# pcb-full.net
KiCad netlist of a schematic drawn in EAGLE
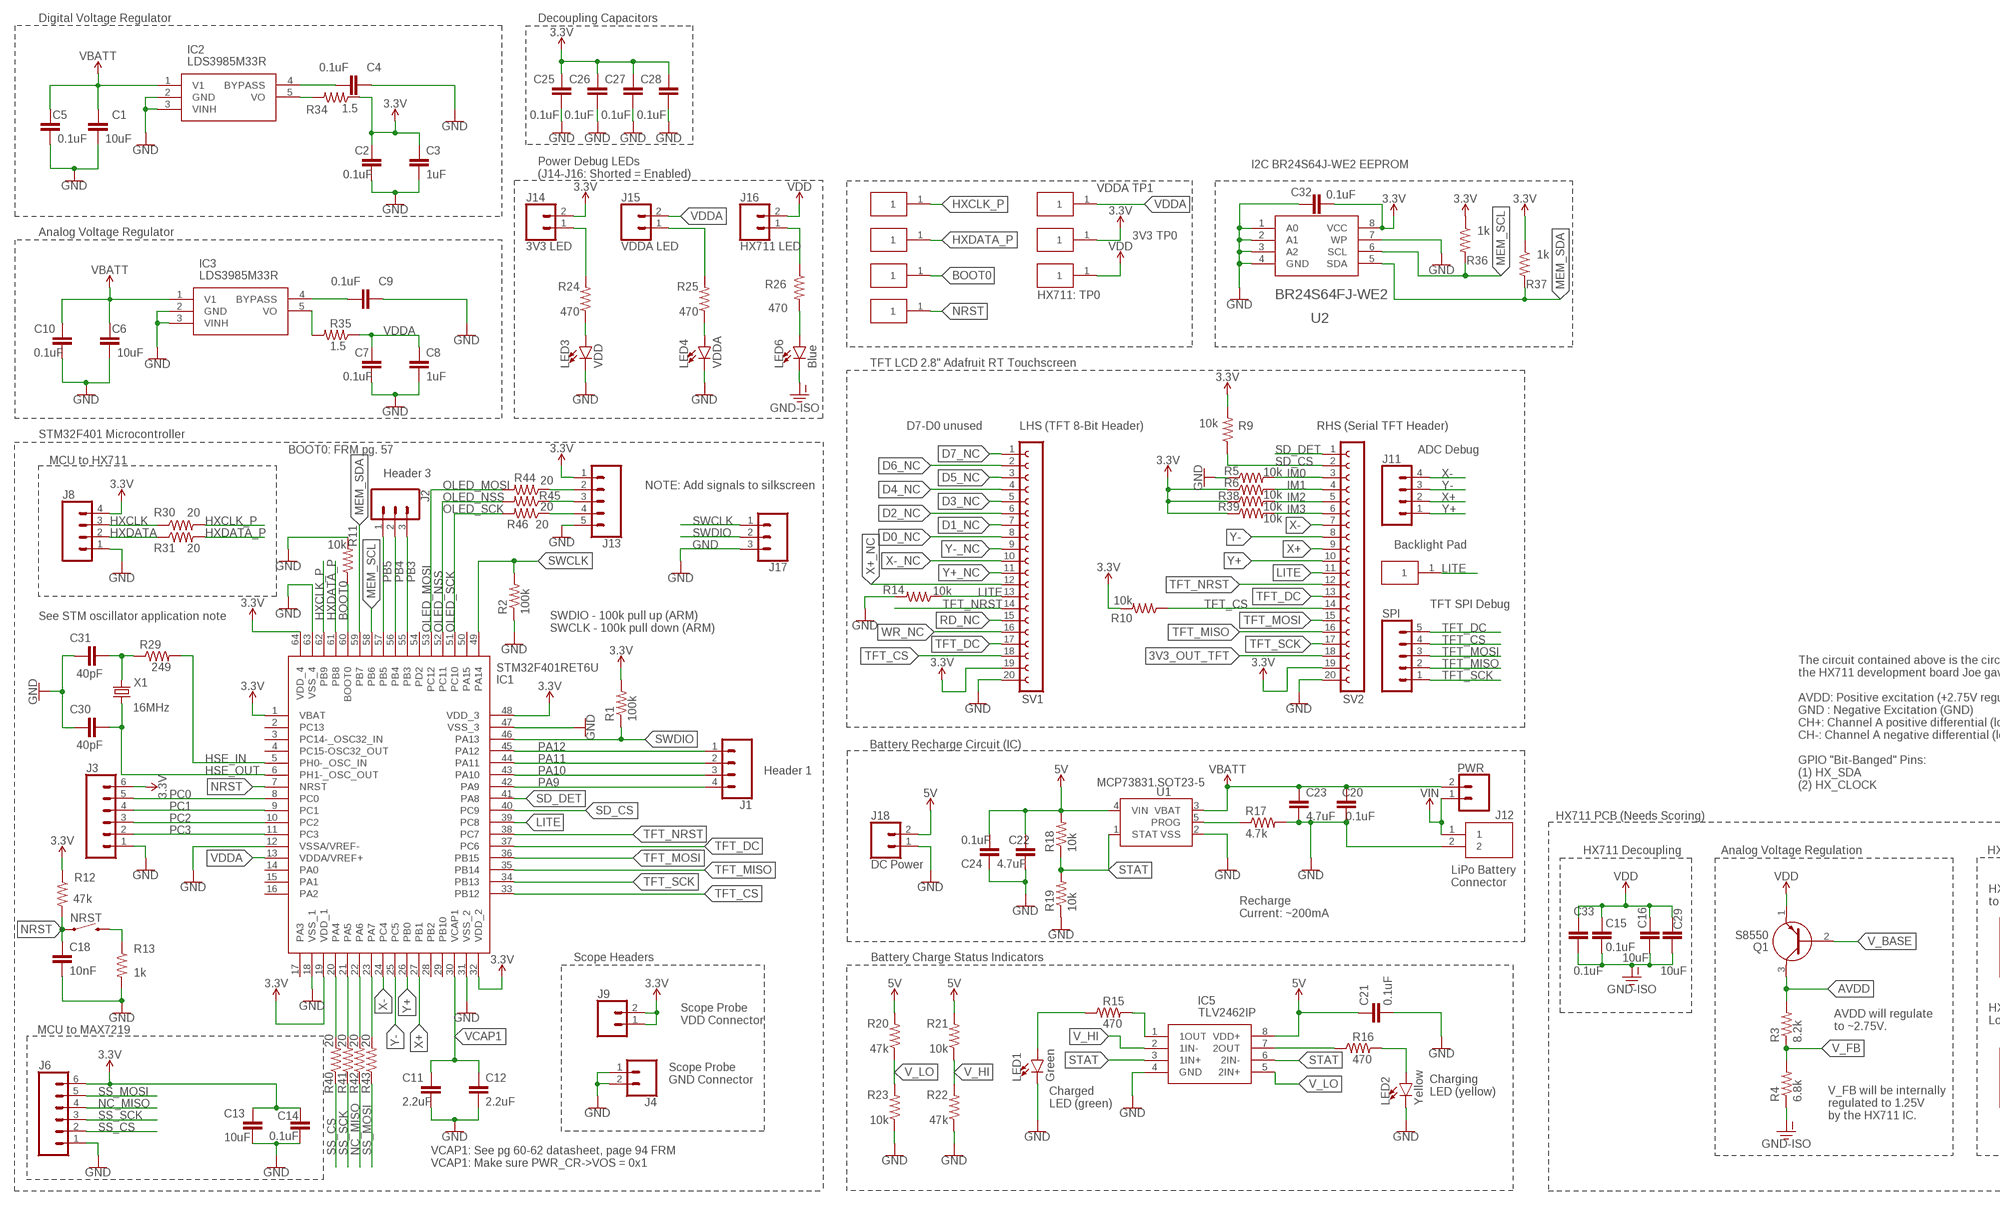
[diagram p0: schematic, sheet 1, part 1 of 2]
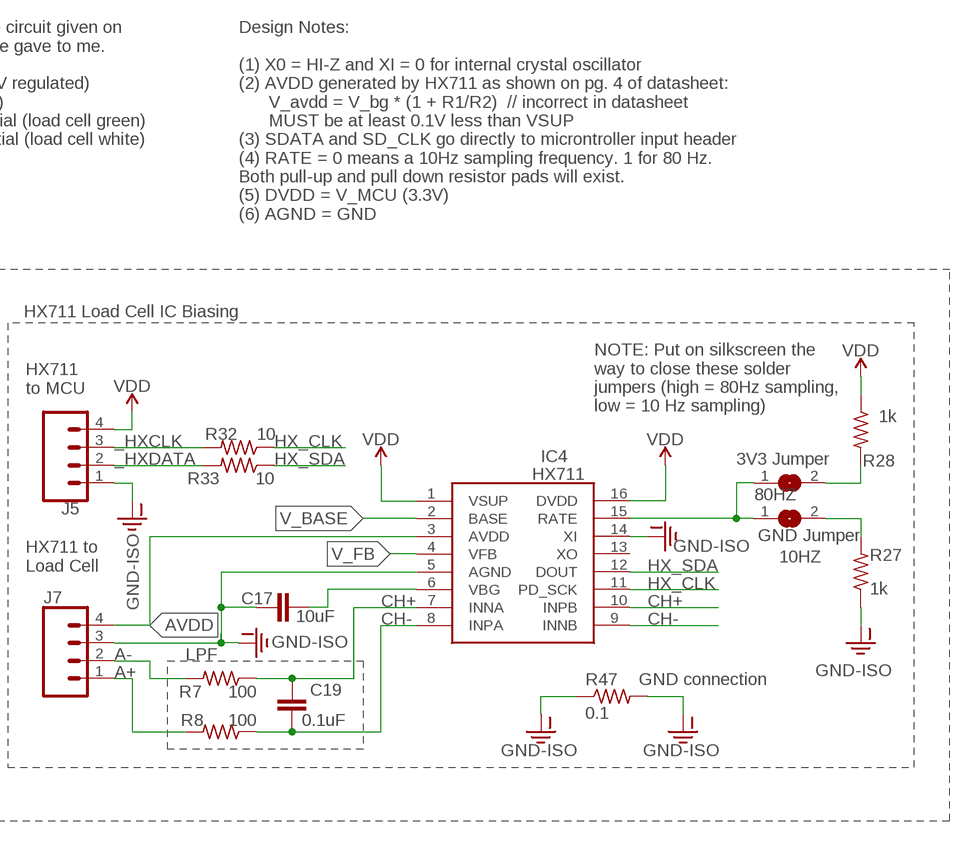
[diagram p1: schematic, sheet 1, part 2 of 2]

(export (version "E")
  (design (tool "Eeschema 10.0.6"))
  (components
    (comp (ref "10HZ")
      (value "GND Jumper")
      (footprint "eagle-import:SJ")
      (libsource (lib "eagle-import") (part "SJ"))
    )
    (comp (ref "80HZ")
      (value "3V3 Jumper")
      (footprint "eagle-import:SJ")
      (libsource (lib "eagle-import") (part "SJ"))
    )
    (comp (ref "C1")
      (value "10uF")
      (footprint "eagle-import:C0603")
      (libsource (lib "eagle-import") (part "CAPACITOR0603"))
    )
    (comp (ref "C2")
      (value "0.1uF")
      (footprint "eagle-import:C0603")
      (libsource (lib "eagle-import") (part "CAPACITOR0603"))
    )
    (comp (ref "C3")
      (value "1uF")
      (footprint "eagle-import:C0603")
      (libsource (lib "eagle-import") (part "CAPACITOR0603"))
    )
    (comp (ref "C4")
      (value "0.1uF")
      (footprint "eagle-import:C0603")
      (libsource (lib "eagle-import") (part "CAPACITOR0603"))
    )
    (comp (ref "C5")
      (value "0.1uF")
      (footprint "eagle-import:C0603")
      (libsource (lib "eagle-import") (part "CAPACITOR0603"))
    )
    (comp (ref "C6")
      (value "10uF")
      (footprint "eagle-import:C0603")
      (libsource (lib "eagle-import") (part "CAPACITOR0603"))
    )
    (comp (ref "C7")
      (value "0.1uF")
      (footprint "eagle-import:C0603")
      (libsource (lib "eagle-import") (part "CAPACITOR0603"))
    )
    (comp (ref "C8")
      (value "1uF")
      (footprint "eagle-import:C0603")
      (libsource (lib "eagle-import") (part "CAPACITOR0603"))
    )
    (comp (ref "C9")
      (value "0.1uF")
      (footprint "eagle-import:C0603")
      (libsource (lib "eagle-import") (part "CAPACITOR0603"))
    )
    (comp (ref "C10")
      (value "0.1uF")
      (footprint "eagle-import:C0603")
      (libsource (lib "eagle-import") (part "CAPACITOR0603"))
    )
    (comp (ref "C11")
      (value "2.2uF")
      (footprint "eagle-import:C0603")
      (libsource (lib "eagle-import") (part "CAPACITOR0603"))
    )
    (comp (ref "C12")
      (value "2.2uF")
      (footprint "eagle-import:C0603")
      (libsource (lib "eagle-import") (part "CAPACITOR0603"))
    )
    (comp (ref "C13")
      (value "10uF")
      (footprint "eagle-import:C0603")
      (libsource (lib "eagle-import") (part "CAPACITOR0603"))
    )
    (comp (ref "C14")
      (value "0.1uF")
      (footprint "eagle-import:C0603")
      (libsource (lib "eagle-import") (part "CAPACITOR0603"))
    )
    (comp (ref "C15")
      (value "0.1uF")
      (footprint "eagle-import:C0603")
      (libsource (lib "eagle-import") (part "CAPACITOR0603"))
    )
    (comp (ref "C16")
      (value "10uF")
      (footprint "eagle-import:C0603")
      (libsource (lib "eagle-import") (part "CAPACITOR0603"))
    )
    (comp (ref "C17")
      (value "10uF")
      (footprint "eagle-import:C0603")
      (libsource (lib "eagle-import") (part "CAPACITOR0603"))
    )
    (comp (ref "C18")
      (value "10nF")
      (footprint "eagle-import:C0603")
      (libsource (lib "eagle-import") (part "CAPACITOR0603"))
    )
    (comp (ref "C19")
      (value "0.1uF")
      (footprint "eagle-import:C0603")
      (libsource (lib "eagle-import") (part "CAPACITOR0603"))
    )
    (comp (ref "C20")
      (value "0.1uF")
      (footprint "eagle-import:C0603")
      (libsource (lib "eagle-import") (part "CAPACITOR0603"))
    )
    (comp (ref "C21")
      (value "0.1uF")
      (footprint "eagle-import:C0603")
      (libsource (lib "eagle-import") (part "CAPACITOR0603"))
    )
    (comp (ref "C22")
      (value "4.7uF")
      (footprint "eagle-import:C5B4.5")
      (libsource (lib "eagle-import") (part "C5/4.5"))
    )
    (comp (ref "C23")
      (value "4.7uF")
      (footprint "eagle-import:C5B4.5")
      (libsource (lib "eagle-import") (part "C5/4.5"))
    )
    (comp (ref "C24")
      (value "0.1uF")
      (footprint "eagle-import:C0603")
      (libsource (lib "eagle-import") (part "CAPACITOR0603"))
    )
    (comp (ref "C25")
      (value "0.1uF")
      (footprint "eagle-import:C0603")
      (libsource (lib "eagle-import") (part "CAPACITOR0603"))
    )
    (comp (ref "C26")
      (value "0.1uF")
      (footprint "eagle-import:C0603")
      (libsource (lib "eagle-import") (part "CAPACITOR0603"))
    )
    (comp (ref "C27")
      (value "0.1uF")
      (footprint "eagle-import:C0603")
      (libsource (lib "eagle-import") (part "CAPACITOR0603"))
    )
    (comp (ref "C28")
      (value "0.1uF")
      (footprint "eagle-import:C0603")
      (libsource (lib "eagle-import") (part "CAPACITOR0603"))
    )
    (comp (ref "C29")
      (value "10uF")
      (footprint "eagle-import:C0603")
      (libsource (lib "eagle-import") (part "CAPACITOR0603"))
    )
    (comp (ref "C30")
      (value "40pF")
      (footprint "eagle-import:C0603")
      (libsource (lib "eagle-import") (part "CAPACITOR0603"))
    )
    (comp (ref "C31")
      (value "40pF")
      (footprint "eagle-import:C0603")
      (libsource (lib "eagle-import") (part "CAPACITOR0603"))
    )
    (comp (ref "C32")
      (value "0.1uF")
      (footprint "eagle-import:C0603")
      (libsource (lib "eagle-import") (part "CAPACITOR0603"))
    )
    (comp (ref "C33")
      (value "0.1uF")
      (footprint "eagle-import:C0603")
      (libsource (lib "eagle-import") (part "CAPACITOR0603"))
    )
    (comp (ref "IC1")
      (value "STM32F401RET6U")
      (footprint "eagle-import:QFP50P1200X1200X160-64N")
      (fields (field (name "MOUSER_PART_NUMBER") "511-STM32F401RET6U"))
      (libsource (lib "eagle-import") (part "STM32F401RET6U"))
    )
    (comp (ref "IC2")
      (value "LDS3985M33R")
      (footprint "eagle-import:SOT95P280X145-5N")
      (fields (field (name "MOUSER_PART_NUMBER") "511-LDS3985M33R"))
      (libsource (lib "eagle-import") (part "LDS3985M33R"))
    )
    (comp (ref "IC3")
      (value "LDS3985M33R")
      (footprint "eagle-import:SOT95P280X145-5N")
      (fields (field (name "MOUSER_PART_NUMBER") "511-LDS3985M33R"))
      (libsource (lib "eagle-import") (part "LDS3985M33R"))
    )
    (comp (ref "IC4")
      (value "HX711")
      (footprint "eagle-import:SOIC127P600X160-16N")
      (libsource (lib "eagle-import") (part "HX711"))
    )
    (comp (ref "IC5")
      (value "TLV2462IP")
      (footprint "eagle-import:DIP794W53P254L959H508Q8N")
      (fields (field (name "MOUSER_PART_NUMBER") "595-TLV2462IP"))
      (libsource (lib "eagle-import") (part "TLV2462IP"))
    )
    (comp (ref "J1")
      (value "CONN_04")
      (footprint "eagle-import:1X04")
      (libsource (lib "eagle-import") (part "CONN_04"))
    )
    (comp (ref "J2")
      (value "CONN_03")
      (footprint "eagle-import:1X03")
      (libsource (lib "eagle-import") (part "CONN_03"))
    )
    (comp (ref "J3")
      (value "CONN_06SILK_FEMALE_PTH")
      (footprint "eagle-import:1X06")
      (libsource (lib "eagle-import") (part "CONN_06SILK_FEMALE_PTH"))
    )
    (comp (ref "J4")
      (value "CONN_02")
      (footprint "eagle-import:1X02")
      (libsource (lib "eagle-import") (part "CONN_02"))
    )
    (comp (ref "J5")
      (value "CONN_04")
      (footprint "eagle-import:1X04")
      (libsource (lib "eagle-import") (part "CONN_04"))
    )
    (comp (ref "J6")
      (value "CONN_06SILK_FEMALE_PTH")
      (footprint "eagle-import:1X06")
      (libsource (lib "eagle-import") (part "CONN_06SILK_FEMALE_PTH"))
    )
    (comp (ref "J7")
      (value "CONN_04")
      (footprint "eagle-import:1X04")
      (libsource (lib "eagle-import") (part "CONN_04"))
    )
    (comp (ref "J8")
      (value "CONN_04")
      (footprint "eagle-import:1X04")
      (libsource (lib "eagle-import") (part "CONN_04"))
    )
    (comp (ref "J9")
      (value "CONN_02")
      (footprint "eagle-import:1X02")
      (libsource (lib "eagle-import") (part "CONN_02"))
    )
    (comp (ref "J11")
      (value "CONN_04")
      (footprint "eagle-import:1X04")
      (libsource (lib "eagle-import") (part "CONN_04"))
    )
    (comp (ref "J12")
      (value "B2B-PH-K-S_LF__SN_")
      (footprint "eagle-import:SHDR2W50P0X200_1X2_590X450X600")
      (fields (field (name "ARROW_PART_NUMBER") "B2B-PH-K-S(LF)(SN)"))
      (libsource (lib "eagle-import") (part "B2B-PH-K-S_LF__SN_"))
    )
    (comp (ref "J13")
      (value "CONN_05")
      (footprint "eagle-import:1X05")
      (libsource (lib "eagle-import") (part "CONN_05"))
    )
    (comp (ref "J14")
      (value "3V3 LED")
      (footprint "eagle-import:1X02")
      (libsource (lib "eagle-import") (part "CONN_02"))
    )
    (comp (ref "J15")
      (value "VDDA LED")
      (footprint "eagle-import:1X02")
      (libsource (lib "eagle-import") (part "CONN_02"))
    )
    (comp (ref "J16")
      (value "HX711 LED")
      (footprint "eagle-import:1X02")
      (libsource (lib "eagle-import") (part "CONN_02"))
    )
    (comp (ref "J17")
      (value "CONN_03")
      (footprint "eagle-import:1X03")
      (libsource (lib "eagle-import") (part "CONN_03"))
    )
    (comp (ref "J18")
      (value "DC Power")
      (footprint "eagle-import:1X02")
      (libsource (lib "eagle-import") (part "CONN_02"))
    )
    (comp (ref "LED1")
      (value "Green")
      (footprint "eagle-import:LED-0603")
      (libsource (lib "eagle-import") (part "LED0603"))
    )
    (comp (ref "LED2")
      (value "Yellow")
      (footprint "eagle-import:LED-0603")
      (libsource (lib "eagle-import") (part "LED0603"))
    )
    (comp (ref "LED3")
      (value "VDD")
      (footprint "eagle-import:LED-0603")
      (libsource (lib "eagle-import") (part "LED0603"))
    )
    (comp (ref "LED4")
      (value "VDDA")
      (footprint "eagle-import:LED-0603")
      (libsource (lib "eagle-import") (part "LED0603"))
    )
    (comp (ref "LED6")
      (value "Blue")
      (footprint "eagle-import:LED-0603")
      (libsource (lib "eagle-import") (part "LED0603"))
    )
    (comp (ref "NRST")
      (value "MOMENTARY-SWITCH-SPST-SMD-5.2-REDUNDANT")
      (footprint "eagle-import:TACTILE_SWITCH_SMD_5.2MM")
      (libsource (lib "eagle-import") (part "MOMENTARY-SWITCH-SPST-SMD-5.2-REDUNDANT"))
    )
    (comp (ref "PWR")
      (value "CONN_02")
      (footprint "eagle-import:1X02")
      (libsource (lib "eagle-import") (part "CONN_02"))
    )
    (comp (ref "Q1")
      (value "S8550")
      (footprint "eagle-import:MJE13001TP")
      (libsource (lib "eagle-import") (part "S8550"))
    )
    (comp (ref "R1")
      (value "100k")
      (footprint "eagle-import:R0603")
      (libsource (lib "eagle-import") (part "RESISTOR0603"))
    )
    (comp (ref "R2")
      (value "100k")
      (footprint "eagle-import:R0603")
      (libsource (lib "eagle-import") (part "RESISTOR0603"))
    )
    (comp (ref "R3")
      (value "8.2k")
      (footprint "eagle-import:R0603")
      (libsource (lib "eagle-import") (part "RESISTOR0603"))
    )
    (comp (ref "R4")
      (value "6.8k")
      (footprint "eagle-import:R0603")
      (libsource (lib "eagle-import") (part "RESISTOR0603"))
    )
    (comp (ref "R5")
      (value "10k")
      (footprint "eagle-import:R0603")
      (libsource (lib "eagle-import") (part "RESISTOR0603"))
    )
    (comp (ref "R6")
      (value "10k")
      (footprint "eagle-import:R0603")
      (libsource (lib "eagle-import") (part "RESISTOR0603"))
    )
    (comp (ref "R7")
      (value "100")
      (footprint "eagle-import:R0603")
      (libsource (lib "eagle-import") (part "RESISTOR0603"))
    )
    (comp (ref "R8")
      (value "100")
      (footprint "eagle-import:R0603")
      (libsource (lib "eagle-import") (part "RESISTOR0603"))
    )
    (comp (ref "R9")
      (value "10k")
      (footprint "eagle-import:R0603")
      (libsource (lib "eagle-import") (part "RESISTOR0603"))
    )
    (comp (ref "R10")
      (value "10k")
      (footprint "eagle-import:R0603")
      (libsource (lib "eagle-import") (part "RESISTOR0603"))
    )
    (comp (ref "R11")
      (value "10k")
      (footprint "eagle-import:R0603")
      (libsource (lib "eagle-import") (part "RESISTOR0603"))
    )
    (comp (ref "R12")
      (value "47k")
      (footprint "eagle-import:R0603")
      (libsource (lib "eagle-import") (part "RESISTOR0603"))
    )
    (comp (ref "R13")
      (value "1k")
      (footprint "eagle-import:R0603")
      (libsource (lib "eagle-import") (part "RESISTOR0603"))
    )
    (comp (ref "R14")
      (value "10k")
      (footprint "eagle-import:R0603")
      (libsource (lib "eagle-import") (part "RESISTOR0603"))
    )
    (comp (ref "R15")
      (value "470")
      (footprint "eagle-import:R0603")
      (libsource (lib "eagle-import") (part "RESISTOR0603"))
    )
    (comp (ref "R16")
      (value "470")
      (footprint "eagle-import:R0603")
      (libsource (lib "eagle-import") (part "RESISTOR0603"))
    )
    (comp (ref "R17")
      (value "4.7k")
      (footprint "eagle-import:R0603")
      (libsource (lib "eagle-import") (part "RESISTOR0603"))
    )
    (comp (ref "R18")
      (value "10k")
      (footprint "eagle-import:R0603")
      (libsource (lib "eagle-import") (part "RESISTOR0603"))
    )
    (comp (ref "R19")
      (value "10k")
      (footprint "eagle-import:R0603")
      (libsource (lib "eagle-import") (part "RESISTOR0603"))
    )
    (comp (ref "R20")
      (value "47k")
      (footprint "eagle-import:R0603")
      (libsource (lib "eagle-import") (part "RESISTOR0603"))
    )
    (comp (ref "R21")
      (value "10k")
      (footprint "eagle-import:R0603")
      (libsource (lib "eagle-import") (part "RESISTOR0603"))
    )
    (comp (ref "R22")
      (value "47k")
      (footprint "eagle-import:R0603")
      (libsource (lib "eagle-import") (part "RESISTOR0603"))
    )
    (comp (ref "R23")
      (value "10k")
      (footprint "eagle-import:R0603")
      (libsource (lib "eagle-import") (part "RESISTOR0603"))
    )
    (comp (ref "R24")
      (value "470")
      (footprint "eagle-import:R0603")
      (libsource (lib "eagle-import") (part "RESISTOR0603"))
    )
    (comp (ref "R25")
      (value "470")
      (footprint "eagle-import:R0603")
      (libsource (lib "eagle-import") (part "RESISTOR0603"))
    )
    (comp (ref "R26")
      (value "470")
      (footprint "eagle-import:R0603")
      (libsource (lib "eagle-import") (part "RESISTOR0603"))
    )
    (comp (ref "R27")
      (value "1k")
      (footprint "eagle-import:R0603")
      (libsource (lib "eagle-import") (part "RESISTOR0603"))
    )
    (comp (ref "R28")
      (value "1k")
      (footprint "eagle-import:R0603")
      (libsource (lib "eagle-import") (part "RESISTOR0603"))
    )
    (comp (ref "R29")
      (value "249")
      (footprint "eagle-import:R0603")
      (libsource (lib "eagle-import") (part "RESISTOR0603"))
    )
    (comp (ref "R30")
      (value "20")
      (footprint "eagle-import:R0603")
      (libsource (lib "eagle-import") (part "RESISTOR0603"))
    )
    (comp (ref "R31")
      (value "20")
      (footprint "eagle-import:R0603")
      (libsource (lib "eagle-import") (part "RESISTOR0603"))
    )
    (comp (ref "R32")
      (value "10")
      (footprint "eagle-import:R0603")
      (libsource (lib "eagle-import") (part "RESISTOR0603"))
    )
    (comp (ref "R33")
      (value "10")
      (footprint "eagle-import:R0603")
      (libsource (lib "eagle-import") (part "RESISTOR0603"))
    )
    (comp (ref "R34")
      (value "1.5")
      (footprint "eagle-import:R0603")
      (libsource (lib "eagle-import") (part "RESISTOR0603"))
    )
    (comp (ref "R35")
      (value "1.5")
      (footprint "eagle-import:R0603")
      (libsource (lib "eagle-import") (part "RESISTOR0603"))
    )
    (comp (ref "R36")
      (value "1k")
      (footprint "eagle-import:R0603")
      (libsource (lib "eagle-import") (part "RESISTOR0603"))
    )
    (comp (ref "R37")
      (value "1k")
      (footprint "eagle-import:R0603")
      (libsource (lib "eagle-import") (part "RESISTOR0603"))
    )
    (comp (ref "R38")
      (value "10k")
      (footprint "eagle-import:R0603")
      (libsource (lib "eagle-import") (part "RESISTOR0603"))
    )
    (comp (ref "R39")
      (value "10k")
      (footprint "eagle-import:R0603")
      (libsource (lib "eagle-import") (part "RESISTOR0603"))
    )
    (comp (ref "R40")
      (value "20")
      (footprint "eagle-import:R0603")
      (libsource (lib "eagle-import") (part "RESISTOR0603"))
    )
    (comp (ref "R41")
      (value "20")
      (footprint "eagle-import:R0603")
      (libsource (lib "eagle-import") (part "RESISTOR0603"))
    )
    (comp (ref "R42")
      (value "20")
      (footprint "eagle-import:R0603")
      (libsource (lib "eagle-import") (part "RESISTOR0603"))
    )
    (comp (ref "R43")
      (value "20")
      (footprint "eagle-import:R0603")
      (libsource (lib "eagle-import") (part "RESISTOR0603"))
    )
    (comp (ref "R44")
      (value "20")
      (footprint "eagle-import:R0603")
      (libsource (lib "eagle-import") (part "RESISTOR0603"))
    )
    (comp (ref "R45")
      (value "20")
      (footprint "eagle-import:R0603")
      (libsource (lib "eagle-import") (part "RESISTOR0603"))
    )
    (comp (ref "R46")
      (value "20")
      (footprint "eagle-import:R0603")
      (libsource (lib "eagle-import") (part "RESISTOR0603"))
    )
    (comp (ref "R47")
      (value "0.1")
      (footprint "eagle-import:R0603")
      (libsource (lib "eagle-import") (part "RESISTOR0603"))
    )
    (comp (ref "SPI")
      (value "CONN_05")
      (footprint "eagle-import:1X05")
      (libsource (lib "eagle-import") (part "CONN_05"))
    )
    (comp (ref "SV1")
      (value "LHS (TFT 8-Bit Header)")
      (footprint "eagle-import:FE20")
      (libsource (lib "eagle-import") (part "FE20-1"))
    )
    (comp (ref "SV2")
      (value "RHS (Serial TFT Header)")
      (footprint "eagle-import:FE20")
      (libsource (lib "eagle-import") (part "FE20-1"))
    )
    (comp (ref "U$1")
      (value "TP1")
      (footprint "eagle-import:PAD")
      (libsource (lib "eagle-import") (part "PAD"))
    )
    (comp (ref "U$2")
      (value "TP3")
      (footprint "eagle-import:PAD")
      (libsource (lib "eagle-import") (part "PAD"))
    )
    (comp (ref "U$3")
      (value "TP4")
      (footprint "eagle-import:PAD")
      (libsource (lib "eagle-import") (part "PAD"))
    )
    (comp (ref "U$4")
      (value "TP5")
      (footprint "eagle-import:PAD")
      (libsource (lib "eagle-import") (part "PAD"))
    )
    (comp (ref "U$5")
      (value "TP6")
      (footprint "eagle-import:PAD")
      (libsource (lib "eagle-import") (part "PAD"))
    )
    (comp (ref "U$6")
      (value "TP1")
      (footprint "eagle-import:PAD")
      (libsource (lib "eagle-import") (part "PAD"))
    )
    (comp (ref "U$7")
      (value "TP0")
      (footprint "eagle-import:PAD")
      (libsource (lib "eagle-import") (part "PAD"))
    )
    (comp (ref "U$8")
      (value "TP2")
      (footprint "eagle-import:PAD")
      (libsource (lib "eagle-import") (part "PAD"))
    )
    (comp (ref "U1")
      (value "MCP73831.SOT23-5")
      (footprint "eagle-import:SOT23-5")
      (libsource (lib "eagle-import") (part "MCP73831.SOT23-5"))
    )
    (comp (ref "U2")
      (value "BR24S64FJ-WE2")
      (footprint "eagle-import:SOIC8")
      (libsource (lib "eagle-import") (part "BR24S64FJ-WE2"))
    )
    (comp (ref "X1")
      (value "16MHz")
      (footprint "eagle-import:HC49_S")
      (libsource (lib "eagle-import") (part "CRYSTALHC49S"))
    )
  )
  (nets
    (net (code "1") (name "/A+") (class "Default")
      (node (ref "J7") (pin "1") (pinfunction "1_1") (pintype "passive"))
      (node (ref "R8") (pin "2") (pinfunction "2_2") (pintype "passive"))
    )
    (net (code "2") (name "/A-") (class "Default")
      (node (ref "J7") (pin "2") (pinfunction "2_2") (pintype "passive"))
      (node (ref "R7") (pin "2") (pinfunction "2_2") (pintype "passive"))
    )
    (net (code "3") (name "/CH+") (class "Default")
      (node (ref "C19") (pin "1") (pinfunction "1_1") (pintype "passive"))
      (node (ref "IC4") (pin "10") (pinfunction "INPB_10") (pintype "bidirectional"))
      (node (ref "IC4") (pin "7") (pinfunction "INNA_7") (pintype "bidirectional"))
      (node (ref "R7") (pin "1") (pinfunction "1_1") (pintype "passive"))
    )
    (net (code "4") (name "/CH-") (class "Default")
      (node (ref "C19") (pin "2") (pinfunction "2_2") (pintype "passive"))
      (node (ref "IC4") (pin "8") (pinfunction "INPA_8") (pintype "bidirectional"))
      (node (ref "IC4") (pin "9") (pinfunction "INNB_9") (pintype "bidirectional"))
      (node (ref "R8") (pin "1") (pinfunction "1_1") (pintype "passive"))
    )
    (net (code "5") (name "/HSE_IN") (class "Default")
      (node (ref "IC1") (pin "5") (pinfunction "PH0-_OSC_IN_5") (pintype "bidirectional"))
      (node (ref "R29") (pin "2") (pinfunction "2_2") (pintype "passive"))
    )
    (net (code "6") (name "/HSE_OUT") (class "Default")
      (node (ref "C30") (pin "2") (pinfunction "2_2") (pintype "passive"))
      (node (ref "IC1") (pin "6") (pinfunction "PH1-_OSC_OUT_6") (pintype "bidirectional"))
      (node (ref "X1") (pin "1") (pinfunction "1_1") (pintype "passive"))
    )
    (net (code "7") (name "/HXCLK") (class "Default")
      (node (ref "J8") (pin "3") (pinfunction "3_3") (pintype "passive"))
      (node (ref "R30") (pin "1") (pinfunction "1_1") (pintype "passive"))
    )
    (net (code "8") (name "/HXDATA") (class "Default")
      (node (ref "J8") (pin "2") (pinfunction "2_2") (pintype "passive"))
      (node (ref "R31") (pin "1") (pinfunction "1_1") (pintype "passive"))
    )
    (net (code "9") (name "/HX_CLK") (class "Default")
      (node (ref "IC4") (pin "11") (pinfunction "PD_SCK_11") (pintype "bidirectional"))
      (node (ref "R32") (pin "1") (pinfunction "1_1") (pintype "passive"))
    )
    (net (code "10") (name "/HX_SDA") (class "Default")
      (node (ref "IC4") (pin "12") (pinfunction "DOUT_12") (pintype "bidirectional"))
      (node (ref "R33") (pin "1") (pinfunction "1_1") (pintype "passive"))
    )
    (net (code "11") (name "/IM0") (class "Default")
      (node (ref "R5") (pin "2") (pinfunction "2_2") (pintype "passive"))
      (node (ref "SV2") (pin "3") (pinfunction "3_3") (pintype "passive"))
    )
    (net (code "12") (name "/IM1") (class "Default")
      (node (ref "R6") (pin "2") (pinfunction "2_2") (pintype "passive"))
      (node (ref "SV2") (pin "4") (pinfunction "4_4") (pintype "passive"))
    )
    (net (code "13") (name "/IM2") (class "Default")
      (node (ref "R38") (pin "2") (pinfunction "2_2") (pintype "passive"))
      (node (ref "SV2") (pin "5") (pinfunction "5_5") (pintype "passive"))
    )
    (net (code "14") (name "/IM3") (class "Default")
      (node (ref "R39") (pin "2") (pinfunction "2_2") (pintype "passive"))
      (node (ref "SV2") (pin "6") (pinfunction "6_6") (pintype "passive"))
    )
    (net (code "15") (name "/NC_MISO") (class "Default")
      (node (ref "J6") (pin "4") (pinfunction "4_4") (pintype "passive"))
      (node (ref "R42") (pin "1") (pinfunction "1_1") (pintype "passive"))
    )
    (net (code "16") (name "/OLED_MOSI") (class "Default")
      (node (ref "IC1") (pin "53") (pinfunction "PC12_53") (pintype "bidirectional"))
      (node (ref "R44") (pin "2") (pinfunction "2_2") (pintype "passive"))
    )
    (net (code "17") (name "/OLED_NSS") (class "Default")
      (node (ref "IC1") (pin "52") (pinfunction "PC11_52") (pintype "bidirectional"))
      (node (ref "R45") (pin "2") (pinfunction "2_2") (pintype "passive"))
    )
    (net (code "18") (name "/OLED_SCK") (class "Default")
      (node (ref "IC1") (pin "51") (pinfunction "PC10_51") (pintype "bidirectional"))
      (node (ref "R46") (pin "2") (pinfunction "2_2") (pintype "passive"))
    )
    (net (code "19") (name "/PA9") (class "Default")
      (node (ref "IC1") (pin "42") (pinfunction "PA9_42") (pintype "bidirectional"))
      (node (ref "J1") (pin "4") (pinfunction "4_4") (pintype "passive"))
    )
    (net (code "20") (name "/PA10") (class "Default")
      (node (ref "IC1") (pin "43") (pinfunction "PA10_43") (pintype "bidirectional"))
      (node (ref "J1") (pin "3") (pinfunction "3_3") (pintype "passive"))
    )
    (net (code "21") (name "/PA11") (class "Default")
      (node (ref "IC1") (pin "44") (pinfunction "PA11_44") (pintype "bidirectional"))
      (node (ref "J1") (pin "2") (pinfunction "2_2") (pintype "passive"))
    )
    (net (code "22") (name "/PA12") (class "Default")
      (node (ref "IC1") (pin "45") (pinfunction "PA12_45") (pintype "bidirectional"))
      (node (ref "J1") (pin "1") (pinfunction "1_1") (pintype "passive"))
    )
    (net (code "23") (name "/PB3") (class "Default")
      (node (ref "IC1") (pin "55") (pinfunction "PB3_55") (pintype "bidirectional"))
      (node (ref "J2") (pin "3") (pinfunction "3_3") (pintype "passive"))
    )
    (net (code "24") (name "/PB4") (class "Default")
      (node (ref "IC1") (pin "56") (pinfunction "PB4_56") (pintype "bidirectional"))
      (node (ref "J2") (pin "2") (pinfunction "2_2") (pintype "passive"))
    )
    (net (code "25") (name "/PB5") (class "Default")
      (node (ref "IC1") (pin "57") (pinfunction "PB5_57") (pintype "bidirectional"))
      (node (ref "J2") (pin "1") (pinfunction "1_1") (pintype "passive"))
    )
    (net (code "26") (name "/PC0") (class "Default")
      (node (ref "IC1") (pin "8") (pinfunction "PC0_8") (pintype "bidirectional"))
      (node (ref "J3") (pin "5") (pinfunction "5_5") (pintype "passive"))
    )
    (net (code "27") (name "/PC1") (class "Default")
      (node (ref "IC1") (pin "9") (pinfunction "PC1_9") (pintype "bidirectional"))
      (node (ref "J3") (pin "4") (pinfunction "4_4") (pintype "passive"))
    )
    (net (code "28") (name "/PC2") (class "Default")
      (node (ref "IC1") (pin "10") (pinfunction "PC2_10") (pintype "bidirectional"))
      (node (ref "J3") (pin "3") (pinfunction "3_3") (pintype "passive"))
    )
    (net (code "29") (name "/PC3") (class "Default")
      (node (ref "IC1") (pin "11") (pinfunction "PC3_11") (pintype "bidirectional"))
      (node (ref "J3") (pin "2") (pinfunction "2_2") (pintype "passive"))
    )
    (net (code "30") (name "/SS_CS") (class "Default")
      (node (ref "J6") (pin "2") (pinfunction "2_2") (pintype "passive"))
      (node (ref "R40") (pin "1") (pinfunction "1_1") (pintype "passive"))
    )
    (net (code "31") (name "/SS_MOSI") (class "Default")
      (node (ref "J6") (pin "5") (pinfunction "5_5") (pintype "passive"))
      (node (ref "R43") (pin "1") (pinfunction "1_1") (pintype "passive"))
    )
    (net (code "32") (name "/SS_SCK") (class "Default")
      (node (ref "J6") (pin "3") (pinfunction "3_3") (pintype "passive"))
      (node (ref "R41") (pin "1") (pinfunction "1_1") (pintype "passive"))
    )
    (net (code "33") (name "/_HXCLK") (class "Default")
      (node (ref "J5") (pin "3") (pinfunction "3_3") (pintype "passive"))
      (node (ref "R32") (pin "2") (pinfunction "2_2") (pintype "passive"))
    )
    (net (code "34") (name "/_HXDATA") (class "Default")
      (node (ref "J5") (pin "2") (pinfunction "2_2") (pintype "passive"))
      (node (ref "R33") (pin "2") (pinfunction "2_2") (pintype "passive"))
    )
    (net (code "35") (name "3.3V") (class "Default")
      (node (ref "C13") (pin "1") (pinfunction "1_1") (pintype "passive"))
      (node (ref "C14") (pin "1") (pinfunction "1_1") (pintype "passive"))
      (node (ref "C2") (pin "1") (pinfunction "1_1") (pintype "passive"))
      (node (ref "C25") (pin "1") (pinfunction "1_1") (pintype "passive"))
      (node (ref "C26") (pin "1") (pinfunction "1_1") (pintype "passive"))
      (node (ref "C27") (pin "1") (pinfunction "1_1") (pintype "passive"))
      (node (ref "C28") (pin "1") (pinfunction "1_1") (pintype "passive"))
      (node (ref "C3") (pin "1") (pinfunction "1_1") (pintype "passive"))
      (node (ref "C32") (pin "2") (pinfunction "2_2") (pintype "passive"))
      (node (ref "IC1") (pin "1") (pinfunction "VBAT_1") (pintype "bidirectional"))
      (node (ref "IC1") (pin "19") (pinfunction "VDD_1_19") (pintype "bidirectional"))
      (node (ref "IC1") (pin "32") (pinfunction "VDD_2_32") (pintype "bidirectional"))
      (node (ref "IC1") (pin "48") (pinfunction "VDD_3_48") (pintype "bidirectional"))
      (node (ref "IC1") (pin "64") (pinfunction "VDD_4_64") (pintype "bidirectional"))
      (node (ref "J13") (pin "1") (pinfunction "1_1") (pintype "passive"))
      (node (ref "J14") (pin "2") (pinfunction "2_2") (pintype "passive"))
      (node (ref "J3") (pin "6") (pinfunction "6_6") (pintype "passive"))
      (node (ref "J6") (pin "6") (pinfunction "6_6") (pintype "passive"))
      (node (ref "J8") (pin "4") (pinfunction "4_4") (pintype "passive"))
      (node (ref "J9") (pin "1") (pinfunction "1_1") (pintype "passive"))
      (node (ref "J9") (pin "2") (pinfunction "2_2") (pintype "passive"))
      (node (ref "R1") (pin "2") (pinfunction "2_2") (pintype "passive"))
      (node (ref "R10") (pin "2") (pinfunction "2_2") (pintype "passive"))
      (node (ref "R12") (pin "1") (pinfunction "1_1") (pintype "passive"))
      (node (ref "R34") (pin "1") (pinfunction "1_1") (pintype "passive"))
      (node (ref "R36") (pin "1") (pinfunction "1_1") (pintype "passive"))
      (node (ref "R37") (pin "1") (pinfunction "1_1") (pintype "passive"))
      (node (ref "R38") (pin "1") (pinfunction "1_1") (pintype "passive"))
      (node (ref "R39") (pin "1") (pinfunction "1_1") (pintype "passive"))
      (node (ref "R6") (pin "1") (pinfunction "1_1") (pintype "passive"))
      (node (ref "R9") (pin "2") (pinfunction "2_2") (pintype "passive"))
      (node (ref "SV1") (pin "19") (pinfunction "19_19") (pintype "passive"))
      (node (ref "SV2") (pin "19") (pinfunction "19_19") (pintype "passive"))
      (node (ref "U$7") (pin "1") (pinfunction "1_1") (pintype "bidirectional"))
      (node (ref "U2") (pin "8") (pinfunction "VCC_8") (pintype "power_in"))
    )
    (net (code "36") (name "3V3_OUT_TFT") (class "Default")
      (node (ref "SV2") (pin "18") (pinfunction "18_18") (pintype "passive"))
    )
    (net (code "37") (name "5V") (class "Default")
      (node (ref "C21") (pin "1") (pinfunction "1_1") (pintype "passive"))
      (node (ref "C22") (pin "1") (pinfunction "1_1") (pintype "passive"))
      (node (ref "C24") (pin "2") (pinfunction "2_2") (pintype "passive"))
      (node (ref "IC5") (pin "8") (pinfunction "VDD+_8") (pintype "bidirectional"))
      (node (ref "J18") (pin "2") (pinfunction "2_2") (pintype "passive"))
      (node (ref "R18") (pin "2") (pinfunction "2_2") (pintype "passive"))
      (node (ref "R20") (pin "2") (pinfunction "2_2") (pintype "passive"))
      (node (ref "R21") (pin "2") (pinfunction "2_2") (pintype "passive"))
      (node (ref "U1") (pin "4") (pinfunction "VIN_4") (pintype "power_in"))
    )
    (net (code "38") (name "AVDD") (class "Default")
      (node (ref "IC4") (pin "3") (pinfunction "AVDD_3") (pintype "bidirectional"))
      (node (ref "J7") (pin "4") (pinfunction "4_4") (pintype "passive"))
      (node (ref "Q1") (pin "3") (pinfunction "C_3") (pintype "bidirectional"))
      (node (ref "R3") (pin "2") (pinfunction "2_2") (pintype "passive"))
    )
    (net (code "39") (name "BOOT0") (class "Default")
      (node (ref "IC1") (pin "60") (pinfunction "BOOT0_60") (pintype "bidirectional"))
      (node (ref "R11") (pin "1") (pinfunction "1_1") (pintype "passive"))
      (node (ref "U$4") (pin "1") (pinfunction "1_1") (pintype "bidirectional"))
    )
    (net (code "40") (name "D0_NC") (class "Default")
      (node (ref "SV1") (pin "8") (pinfunction "8_8") (pintype "passive"))
    )
    (net (code "41") (name "D1_NC") (class "Default")
      (node (ref "SV1") (pin "7") (pinfunction "7_7") (pintype "passive"))
    )
    (net (code "42") (name "D2_NC") (class "Default")
      (node (ref "SV1") (pin "6") (pinfunction "6_6") (pintype "passive"))
    )
    (net (code "43") (name "D3_NC") (class "Default")
      (node (ref "SV1") (pin "5") (pinfunction "5_5") (pintype "passive"))
    )
    (net (code "44") (name "D4_NC") (class "Default")
      (node (ref "SV1") (pin "4") (pinfunction "4_4") (pintype "passive"))
    )
    (net (code "45") (name "D5_NC") (class "Default")
      (node (ref "SV1") (pin "3") (pinfunction "3_3") (pintype "passive"))
    )
    (net (code "46") (name "D6_NC") (class "Default")
      (node (ref "SV1") (pin "2") (pinfunction "2_2") (pintype "passive"))
    )
    (net (code "47") (name "D7_NC") (class "Default")
      (node (ref "SV1") (pin "1") (pinfunction "1_1") (pintype "passive"))
    )
    (net (code "48") (name "GND") (class "Default")
      (node (ref "C1") (pin "2") (pinfunction "2_2") (pintype "passive"))
      (node (ref "C10") (pin "2") (pinfunction "2_2") (pintype "passive"))
      (node (ref "C11") (pin "2") (pinfunction "2_2") (pintype "passive"))
      (node (ref "C12") (pin "2") (pinfunction "2_2") (pintype "passive"))
      (node (ref "C13") (pin "2") (pinfunction "2_2") (pintype "passive"))
      (node (ref "C14") (pin "2") (pinfunction "2_2") (pintype "passive"))
      (node (ref "C18") (pin "2") (pinfunction "2_2") (pintype "passive"))
      (node (ref "C2") (pin "2") (pinfunction "2_2") (pintype "passive"))
      (node (ref "C20") (pin "2") (pinfunction "2_2") (pintype "passive"))
      (node (ref "C21") (pin "2") (pinfunction "2_2") (pintype "passive"))
      (node (ref "C22") (pin "2") (pinfunction "2_2") (pintype "passive"))
      (node (ref "C23") (pin "2") (pinfunction "2_2") (pintype "passive"))
      (node (ref "C24") (pin "1") (pinfunction "1_1") (pintype "passive"))
      (node (ref "C25") (pin "2") (pinfunction "2_2") (pintype "passive"))
      (node (ref "C26") (pin "2") (pinfunction "2_2") (pintype "passive"))
      (node (ref "C27") (pin "2") (pinfunction "2_2") (pintype "passive"))
      (node (ref "C28") (pin "2") (pinfunction "2_2") (pintype "passive"))
      (node (ref "C3") (pin "2") (pinfunction "2_2") (pintype "passive"))
      (node (ref "C30") (pin "1") (pinfunction "1_1") (pintype "passive"))
      (node (ref "C31") (pin "1") (pinfunction "1_1") (pintype "passive"))
      (node (ref "C32") (pin "1") (pinfunction "1_1") (pintype "passive"))
      (node (ref "C4") (pin "1") (pinfunction "1_1") (pintype "passive"))
      (node (ref "C5") (pin "2") (pinfunction "2_2") (pintype "passive"))
      (node (ref "C6") (pin "2") (pinfunction "2_2") (pintype "passive"))
      (node (ref "C7") (pin "2") (pinfunction "2_2") (pintype "passive"))
      (node (ref "C8") (pin "2") (pinfunction "2_2") (pintype "passive"))
      (node (ref "C9") (pin "1") (pinfunction "1_1") (pintype "passive"))
      (node (ref "IC1") (pin "12") (pinfunction "VSSA/VREF-_12") (pintype "bidirectional"))
      (node (ref "IC1") (pin "18") (pinfunction "VSS_1_18") (pintype "bidirectional"))
      (node (ref "IC1") (pin "31") (pinfunction "VSS_2_31") (pintype "bidirectional"))
      (node (ref "IC1") (pin "47") (pinfunction "VSS_3_47") (pintype "bidirectional"))
      (node (ref "IC1") (pin "63") (pinfunction "VSS_4_63") (pintype "bidirectional"))
      (node (ref "IC2") (pin "2") (pinfunction "GND_2") (pintype "bidirectional"))
      (node (ref "IC2") (pin "3") (pinfunction "VINH_3") (pintype "bidirectional"))
      (node (ref "IC3") (pin "2") (pinfunction "GND_2") (pintype "bidirectional"))
      (node (ref "IC3") (pin "3") (pinfunction "VINH_3") (pintype "bidirectional"))
      (node (ref "IC5") (pin "4") (pinfunction "GND_4") (pintype "bidirectional"))
      (node (ref "J12") (pin "2") (pinfunction "2_2") (pintype "bidirectional"))
      (node (ref "J13") (pin "5") (pinfunction "5_5") (pintype "passive"))
      (node (ref "J17") (pin "3") (pinfunction "3_3") (pintype "passive"))
      (node (ref "J18") (pin "1") (pinfunction "1_1") (pintype "passive"))
      (node (ref "J3") (pin "1") (pinfunction "1_1") (pintype "passive"))
      (node (ref "J4") (pin "1") (pinfunction "1_1") (pintype "passive"))
      (node (ref "J4") (pin "2") (pinfunction "2_2") (pintype "passive"))
      (node (ref "J6") (pin "1") (pinfunction "1_1") (pintype "passive"))
      (node (ref "J8") (pin "1") (pinfunction "1_1") (pintype "passive"))
      (node (ref "LED1") (pin "C") (pinfunction "C_C") (pintype "passive"))
      (node (ref "LED2") (pin "C") (pinfunction "C_C") (pintype "passive"))
      (node (ref "LED3") (pin "C") (pinfunction "C_C") (pintype "passive"))
      (node (ref "LED4") (pin "C") (pinfunction "C_C") (pintype "passive"))
      (node (ref "R11") (pin "2") (pinfunction "2_2") (pintype "passive"))
      (node (ref "R13") (pin "2") (pinfunction "2_2") (pintype "passive"))
      (node (ref "R14") (pin "2") (pinfunction "2_2") (pintype "passive"))
      (node (ref "R17") (pin "2") (pinfunction "2_2") (pintype "passive"))
      (node (ref "R19") (pin "1") (pinfunction "1_1") (pintype "passive"))
      (node (ref "R2") (pin "1") (pinfunction "1_1") (pintype "passive"))
      (node (ref "R22") (pin "1") (pinfunction "1_1") (pintype "passive"))
      (node (ref "R23") (pin "1") (pinfunction "1_1") (pintype "passive"))
      (node (ref "R5") (pin "1") (pinfunction "1_1") (pintype "passive"))
      (node (ref "SV1") (pin "20") (pinfunction "20_20") (pintype "passive"))
      (node (ref "SV2") (pin "20") (pinfunction "20_20") (pintype "passive"))
      (node (ref "U1") (pin "2") (pinfunction "VSS_2") (pintype "power_in"))
      (node (ref "U2") (pin "1") (pinfunction "A0_1") (pintype "bidirectional"))
      (node (ref "U2") (pin "2") (pinfunction "A1_2") (pintype "bidirectional"))
      (node (ref "U2") (pin "3") (pinfunction "A2_3") (pintype "bidirectional"))
      (node (ref "U2") (pin "4") (pinfunction "GND_4") (pintype "power_in"))
      (node (ref "U2") (pin "7") (pinfunction "WP_7") (pintype "bidirectional"))
    )
    (net (code "49") (name "GND-ISO") (class "Default")
      (node (ref "C15") (pin "2") (pinfunction "2_2") (pintype "passive"))
      (node (ref "C16") (pin "2") (pinfunction "2_2") (pintype "passive"))
      (node (ref "C17") (pin "1") (pinfunction "1_1") (pintype "passive"))
      (node (ref "C29") (pin "2") (pinfunction "2_2") (pintype "passive"))
      (node (ref "C33") (pin "2") (pinfunction "2_2") (pintype "passive"))
      (node (ref "IC4") (pin "14") (pinfunction "XI_14") (pintype "bidirectional"))
      (node (ref "IC4") (pin "5") (pinfunction "AGND_5") (pintype "bidirectional"))
      (node (ref "J5") (pin "1") (pinfunction "1_1") (pintype "passive"))
      (node (ref "J7") (pin "3") (pinfunction "3_3") (pintype "passive"))
      (node (ref "LED6") (pin "C") (pinfunction "C_C") (pintype "passive"))
      (node (ref "R27") (pin "1") (pinfunction "1_1") (pintype "passive"))
      (node (ref "R4") (pin "1") (pinfunction "1_1") (pintype "passive"))
      (node (ref "R47") (pin "1") (pinfunction "1_1") (pintype "passive"))
      (node (ref "R47") (pin "2") (pinfunction "2_2") (pintype "passive"))
    )
    (net (code "50") (name "HXCLK_P") (class "Default")
      (node (ref "IC1") (pin "62") (pinfunction "PB9_62") (pintype "bidirectional"))
      (node (ref "R30") (pin "2") (pinfunction "2_2") (pintype "passive"))
      (node (ref "U$2") (pin "1") (pinfunction "1_1") (pintype "bidirectional"))
    )
    (net (code "51") (name "HXDATA_P") (class "Default")
      (node (ref "IC1") (pin "61") (pinfunction "PB8_61") (pintype "bidirectional"))
      (node (ref "R31") (pin "2") (pinfunction "2_2") (pintype "passive"))
      (node (ref "U$3") (pin "1") (pinfunction "1_1") (pintype "bidirectional"))
    )
    (net (code "52") (name "LITE") (class "Default")
      (node (ref "IC1") (pin "39") (pinfunction "PC8_39") (pintype "bidirectional"))
      (node (ref "R14") (pin "1") (pinfunction "1_1") (pintype "passive"))
      (node (ref "SV1") (pin "13") (pinfunction "13_13") (pintype "passive"))
      (node (ref "SV2") (pin "11") (pinfunction "11_11") (pintype "passive"))
      (node (ref "U$1") (pin "1") (pinfunction "1_1") (pintype "bidirectional"))
    )
    (net (code "53") (name "MEM_SCL") (class "Default")
      (node (ref "IC1") (pin "58") (pinfunction "PB6_58") (pintype "bidirectional"))
      (node (ref "R36") (pin "2") (pinfunction "2_2") (pintype "passive"))
      (node (ref "U2") (pin "6") (pinfunction "SCL_6") (pintype "bidirectional"))
    )
    (net (code "54") (name "MEM_SDA") (class "Default")
      (node (ref "IC1") (pin "59") (pinfunction "PB7_59") (pintype "bidirectional"))
      (node (ref "R37") (pin "2") (pinfunction "2_2") (pintype "passive"))
      (node (ref "U2") (pin "5") (pinfunction "SDA_5") (pintype "bidirectional"))
    )
    (net (code "55") (name "NRST") (class "Default")
      (node (ref "C18") (pin "1") (pinfunction "1_1") (pintype "passive"))
      (node (ref "IC1") (pin "7") (pinfunction "NRST_7") (pintype "bidirectional"))
      (node (ref "NRST") (pin "1") (pinfunction "1_1") (pintype "passive"))
      (node (ref "NRST") (pin "2") (pinfunction "1_2") (pintype "passive"))
      (node (ref "R12") (pin "2") (pinfunction "2_2") (pintype "passive"))
      (node (ref "U$5") (pin "1") (pinfunction "1_1") (pintype "bidirectional"))
    )
    (net (code "56") (name "Net-(10HZ-Pad2)") (class "Default")
      (node (ref "10HZ") (pin "2") (pinfunction "2_2") (pintype "passive"))
      (node (ref "R27") (pin "2") (pinfunction "2_2") (pintype "passive"))
    )
    (net (code "57") (name "Net-(80HZ-Pad2)") (class "Default")
      (node (ref "80HZ") (pin "2") (pinfunction "2_2") (pintype "passive"))
      (node (ref "R28") (pin "2") (pinfunction "2_2") (pintype "passive"))
    )
    (net (code "58") (name "Net-(C31-Pad2)") (class "Default")
      (node (ref "C31") (pin "2") (pinfunction "2_2") (pintype "passive"))
      (node (ref "R29") (pin "1") (pinfunction "1_1") (pintype "passive"))
      (node (ref "X1") (pin "2") (pinfunction "2_2") (pintype "passive"))
    )
    (net (code "59") (name "Net-(IC1-PA4)") (class "Default")
      (node (ref "IC1") (pin "20") (pinfunction "PA4_20") (pintype "bidirectional"))
      (node (ref "R40") (pin "2") (pinfunction "2_2") (pintype "passive"))
    )
    (net (code "60") (name "Net-(IC1-PA5)") (class "Default")
      (node (ref "IC1") (pin "21") (pinfunction "PA5_21") (pintype "bidirectional"))
      (node (ref "R41") (pin "2") (pinfunction "2_2") (pintype "passive"))
    )
    (net (code "61") (name "Net-(IC1-PA6)") (class "Default")
      (node (ref "IC1") (pin "22") (pinfunction "PA6_22") (pintype "bidirectional"))
      (node (ref "R42") (pin "2") (pinfunction "2_2") (pintype "passive"))
    )
    (net (code "62") (name "Net-(IC1-PA7)") (class "Default")
      (node (ref "IC1") (pin "23") (pinfunction "PA7_23") (pintype "bidirectional"))
      (node (ref "R43") (pin "2") (pinfunction "2_2") (pintype "passive"))
    )
    (net (code "63") (name "Net-(IC2-BYPASS)") (class "Default")
      (node (ref "C4") (pin "2") (pinfunction "2_2") (pintype "passive"))
      (node (ref "IC2") (pin "4") (pinfunction "BYPASS_4") (pintype "bidirectional"))
    )
    (net (code "64") (name "Net-(IC2-VO)") (class "Default")
      (node (ref "IC2") (pin "5") (pinfunction "VO_5") (pintype "bidirectional"))
      (node (ref "R34") (pin "2") (pinfunction "2_2") (pintype "passive"))
    )
    (net (code "65") (name "Net-(IC3-BYPASS)") (class "Default")
      (node (ref "C9") (pin "2") (pinfunction "2_2") (pintype "passive"))
      (node (ref "IC3") (pin "4") (pinfunction "BYPASS_4") (pintype "bidirectional"))
    )
    (net (code "66") (name "Net-(IC3-VO)") (class "Default")
      (node (ref "IC3") (pin "5") (pinfunction "VO_5") (pintype "bidirectional"))
      (node (ref "R35") (pin "2") (pinfunction "2_2") (pintype "passive"))
    )
    (net (code "67") (name "Net-(IC4-RATE)") (class "Default")
      (node (ref "10HZ") (pin "1") (pinfunction "1_1") (pintype "passive"))
      (node (ref "80HZ") (pin "1") (pinfunction "1_1") (pintype "passive"))
      (node (ref "IC4") (pin "15") (pinfunction "RATE_15") (pintype "bidirectional"))
    )
    (net (code "68") (name "Net-(IC4-VBG)") (class "Default")
      (node (ref "C17") (pin "2") (pinfunction "2_2") (pintype "passive"))
      (node (ref "IC4") (pin "6") (pinfunction "VBG_6") (pintype "bidirectional"))
    )
    (net (code "69") (name "Net-(IC5-1OUT)") (class "Default")
      (node (ref "IC5") (pin "1") (pinfunction "1OUT_1") (pintype "bidirectional"))
      (node (ref "R15") (pin "2") (pinfunction "2_2") (pintype "passive"))
    )
    (net (code "70") (name "Net-(IC5-2OUT)") (class "Default")
      (node (ref "IC5") (pin "7") (pinfunction "2OUT_7") (pintype "bidirectional"))
      (node (ref "R16") (pin "1") (pinfunction "1_1") (pintype "passive"))
    )
    (net (code "71") (name "Net-(J13-Pad2)") (class "Default")
      (node (ref "J13") (pin "2") (pinfunction "2_2") (pintype "passive"))
      (node (ref "R44") (pin "1") (pinfunction "1_1") (pintype "passive"))
    )
    (net (code "72") (name "Net-(J13-Pad3)") (class "Default")
      (node (ref "J13") (pin "3") (pinfunction "3_3") (pintype "passive"))
      (node (ref "R45") (pin "1") (pinfunction "1_1") (pintype "passive"))
    )
    (net (code "73") (name "Net-(J13-Pad4)") (class "Default")
      (node (ref "J13") (pin "4") (pinfunction "4_4") (pintype "passive"))
      (node (ref "R46") (pin "1") (pinfunction "1_1") (pintype "passive"))
    )
    (net (code "74") (name "Net-(J14-Pad1)") (class "Default")
      (node (ref "J14") (pin "1") (pinfunction "1_1") (pintype "passive"))
      (node (ref "R24") (pin "2") (pinfunction "2_2") (pintype "passive"))
    )
    (net (code "75") (name "Net-(J15-Pad1)") (class "Default")
      (node (ref "J15") (pin "1") (pinfunction "1_1") (pintype "passive"))
      (node (ref "R25") (pin "2") (pinfunction "2_2") (pintype "passive"))
    )
    (net (code "76") (name "Net-(J16-Pad1)") (class "Default")
      (node (ref "J16") (pin "1") (pinfunction "1_1") (pintype "passive"))
      (node (ref "R26") (pin "1") (pinfunction "1_1") (pintype "passive"))
    )
    (net (code "77") (name "Net-(LED1-PadA)") (class "Default")
      (node (ref "LED1") (pin "A") (pinfunction "A_A") (pintype "passive"))
      (node (ref "R15") (pin "1") (pinfunction "1_1") (pintype "passive"))
    )
    (net (code "78") (name "Net-(LED2-PadA)") (class "Default")
      (node (ref "LED2") (pin "A") (pinfunction "A_A") (pintype "passive"))
      (node (ref "R16") (pin "2") (pinfunction "2_2") (pintype "passive"))
    )
    (net (code "79") (name "Net-(LED3-PadA)") (class "Default")
      (node (ref "LED3") (pin "A") (pinfunction "A_A") (pintype "passive"))
      (node (ref "R24") (pin "1") (pinfunction "1_1") (pintype "passive"))
    )
    (net (code "80") (name "Net-(LED4-PadA)") (class "Default")
      (node (ref "LED4") (pin "A") (pinfunction "A_A") (pintype "passive"))
      (node (ref "R25") (pin "1") (pinfunction "1_1") (pintype "passive"))
    )
    (net (code "81") (name "Net-(LED6-PadA)") (class "Default")
      (node (ref "LED6") (pin "A") (pinfunction "A_A") (pintype "passive"))
      (node (ref "R26") (pin "2") (pinfunction "2_2") (pintype "passive"))
    )
    (net (code "82") (name "Net-(NRST-2-Pad3)") (class "Default")
      (node (ref "NRST") (pin "3") (pinfunction "2_3") (pintype "passive"))
      (node (ref "NRST") (pin "4") (pinfunction "2_4") (pintype "passive"))
      (node (ref "R13") (pin "1") (pinfunction "1_1") (pintype "passive"))
    )
    (net (code "83") (name "Net-(U1-PROG)") (class "Default")
      (node (ref "R17") (pin "1") (pinfunction "1_1") (pintype "passive"))
      (node (ref "U1") (pin "5") (pinfunction "PROG_5") (pintype "input"))
    )
    (net (code "84") (name "RD_NC") (class "Default")
      (node (ref "SV1") (pin "15") (pinfunction "15_15") (pintype "passive"))
    )
    (net (code "85") (name "SD_CS") (class "Default")
      (node (ref "IC1") (pin "40") (pinfunction "PC9_40") (pintype "bidirectional"))
      (node (ref "R9") (pin "1") (pinfunction "1_1") (pintype "passive"))
      (node (ref "SV2") (pin "2") (pinfunction "2_2") (pintype "passive"))
    )
    (net (code "86") (name "SD_DET") (class "Default")
      (node (ref "IC1") (pin "41") (pinfunction "PA8_41") (pintype "bidirectional"))
      (node (ref "SV2") (pin "1") (pinfunction "1_1") (pintype "passive"))
    )
    (net (code "87") (name "STAT") (class "Default")
      (node (ref "IC5") (pin "3") (pinfunction "1IN+_3") (pintype "bidirectional"))
      (node (ref "IC5") (pin "6") (pinfunction "2IN-_6") (pintype "bidirectional"))
      (node (ref "R18") (pin "1") (pinfunction "1_1") (pintype "passive"))
      (node (ref "R19") (pin "2") (pinfunction "2_2") (pintype "passive"))
      (node (ref "U1") (pin "1") (pinfunction "STAT_1") (pintype "output"))
    )
    (net (code "88") (name "SWCLK") (class "Default")
      (node (ref "IC1") (pin "49") (pinfunction "PA14_49") (pintype "bidirectional"))
      (node (ref "J17") (pin "1") (pinfunction "1_1") (pintype "passive"))
      (node (ref "R2") (pin "2") (pinfunction "2_2") (pintype "passive"))
    )
    (net (code "89") (name "SWDIO") (class "Default")
      (node (ref "IC1") (pin "46") (pinfunction "PA13_46") (pintype "bidirectional"))
      (node (ref "J17") (pin "2") (pinfunction "2_2") (pintype "passive"))
      (node (ref "R1") (pin "1") (pinfunction "1_1") (pintype "passive"))
    )
    (net (code "90") (name "TFT_CS") (class "Default")
      (node (ref "IC1") (pin "33") (pinfunction "PB12_33") (pintype "bidirectional"))
      (node (ref "R10") (pin "1") (pinfunction "1_1") (pintype "passive"))
      (node (ref "SPI") (pin "4") (pinfunction "4_4") (pintype "passive"))
      (node (ref "SV1") (pin "18") (pinfunction "18_18") (pintype "passive"))
      (node (ref "SV2") (pin "14") (pinfunction "14_14") (pintype "passive"))
    )
    (net (code "91") (name "TFT_DC") (class "Default")
      (node (ref "IC1") (pin "37") (pinfunction "PC6_37") (pintype "bidirectional"))
      (node (ref "SPI") (pin "5") (pinfunction "5_5") (pintype "passive"))
      (node (ref "SV1") (pin "17") (pinfunction "17_17") (pintype "passive"))
      (node (ref "SV2") (pin "13") (pinfunction "13_13") (pintype "passive"))
    )
    (net (code "92") (name "TFT_MISO") (class "Default")
      (node (ref "IC1") (pin "35") (pinfunction "PB14_35") (pintype "bidirectional"))
      (node (ref "SPI") (pin "2") (pinfunction "2_2") (pintype "passive"))
      (node (ref "SV2") (pin "16") (pinfunction "16_16") (pintype "passive"))
    )
    (net (code "93") (name "TFT_MOSI") (class "Default")
      (node (ref "IC1") (pin "36") (pinfunction "PB15_36") (pintype "bidirectional"))
      (node (ref "SPI") (pin "3") (pinfunction "3_3") (pintype "passive"))
      (node (ref "SV2") (pin "15") (pinfunction "15_15") (pintype "passive"))
    )
    (net (code "94") (name "TFT_NRST") (class "Default")
      (node (ref "IC1") (pin "38") (pinfunction "PC7_38") (pintype "bidirectional"))
      (node (ref "SV1") (pin "14") (pinfunction "14_14") (pintype "passive"))
      (node (ref "SV2") (pin "12") (pinfunction "12_12") (pintype "passive"))
    )
    (net (code "95") (name "TFT_SCK") (class "Default")
      (node (ref "IC1") (pin "34") (pinfunction "PB13_34") (pintype "bidirectional"))
      (node (ref "SPI") (pin "1") (pinfunction "1_1") (pintype "passive"))
      (node (ref "SV2") (pin "17") (pinfunction "17_17") (pintype "passive"))
    )
    (net (code "96") (name "VBATT") (class "Default")
      (node (ref "C1") (pin "1") (pinfunction "1_1") (pintype "passive"))
      (node (ref "C10") (pin "1") (pinfunction "1_1") (pintype "passive"))
      (node (ref "C20") (pin "1") (pinfunction "1_1") (pintype "passive"))
      (node (ref "C23") (pin "1") (pinfunction "1_1") (pintype "passive"))
      (node (ref "C5") (pin "1") (pinfunction "1_1") (pintype "passive"))
      (node (ref "C6") (pin "1") (pinfunction "1_1") (pintype "passive"))
      (node (ref "IC2") (pin "1") (pinfunction "V1_1") (pintype "bidirectional"))
      (node (ref "IC3") (pin "1") (pinfunction "V1_1") (pintype "bidirectional"))
      (node (ref "PWR") (pin "2") (pinfunction "2_2") (pintype "passive"))
      (node (ref "U1") (pin "3") (pinfunction "VBAT_3") (pintype "power_in"))
    )
    (net (code "97") (name "VCAP1") (class "Default")
      (node (ref "C11") (pin "1") (pinfunction "1_1") (pintype "passive"))
      (node (ref "C12") (pin "1") (pinfunction "1_1") (pintype "passive"))
      (node (ref "IC1") (pin "30") (pinfunction "VCAP1_30") (pintype "bidirectional"))
    )
    (net (code "98") (name "VDD") (class "Default")
      (node (ref "C15") (pin "1") (pinfunction "1_1") (pintype "passive"))
      (node (ref "C16") (pin "1") (pinfunction "1_1") (pintype "passive"))
      (node (ref "C29") (pin "1") (pinfunction "1_1") (pintype "passive"))
      (node (ref "C33") (pin "1") (pinfunction "1_1") (pintype "passive"))
      (node (ref "IC4") (pin "1") (pinfunction "VSUP_1") (pintype "bidirectional"))
      (node (ref "IC4") (pin "16") (pinfunction "DVDD_16") (pintype "bidirectional"))
      (node (ref "J16") (pin "2") (pinfunction "2_2") (pintype "passive"))
      (node (ref "J5") (pin "4") (pinfunction "4_4") (pintype "passive"))
      (node (ref "Q1") (pin "1") (pinfunction "E_1") (pintype "bidirectional"))
      (node (ref "R28") (pin "1") (pinfunction "1_1") (pintype "passive"))
      (node (ref "U$8") (pin "1") (pinfunction "1_1") (pintype "bidirectional"))
    )
    (net (code "99") (name "VDDA") (class "Default")
      (node (ref "C7") (pin "1") (pinfunction "1_1") (pintype "passive"))
      (node (ref "C8") (pin "1") (pinfunction "1_1") (pintype "passive"))
      (node (ref "IC1") (pin "13") (pinfunction "VDDA/VREF+_13") (pintype "bidirectional"))
      (node (ref "J15") (pin "2") (pinfunction "2_2") (pintype "passive"))
      (node (ref "R35") (pin "1") (pinfunction "1_1") (pintype "passive"))
      (node (ref "U$6") (pin "1") (pinfunction "1_1") (pintype "bidirectional"))
    )
    (net (code "100") (name "VIN") (class "Default")
      (node (ref "J12") (pin "1") (pinfunction "1_1") (pintype "bidirectional"))
      (node (ref "PWR") (pin "1") (pinfunction "1_1") (pintype "passive"))
    )
    (net (code "101") (name "V_BASE") (class "Default")
      (node (ref "IC4") (pin "2") (pinfunction "BASE_2") (pintype "bidirectional"))
      (node (ref "Q1") (pin "2") (pinfunction "B_2") (pintype "bidirectional"))
    )
    (net (code "102") (name "V_FB") (class "Default")
      (node (ref "IC4") (pin "4") (pinfunction "VFB_4") (pintype "bidirectional"))
      (node (ref "R3") (pin "1") (pinfunction "1_1") (pintype "passive"))
      (node (ref "R4") (pin "2") (pinfunction "2_2") (pintype "passive"))
    )
    (net (code "103") (name "V_HI") (class "Default")
      (node (ref "IC5") (pin "2") (pinfunction "1IN-_2") (pintype "bidirectional"))
      (node (ref "R21") (pin "1") (pinfunction "1_1") (pintype "passive"))
      (node (ref "R22") (pin "2") (pinfunction "2_2") (pintype "passive"))
    )
    (net (code "104") (name "V_LO") (class "Default")
      (node (ref "IC5") (pin "5") (pinfunction "2IN+_5") (pintype "bidirectional"))
      (node (ref "R20") (pin "1") (pinfunction "1_1") (pintype "passive"))
      (node (ref "R23") (pin "2") (pinfunction "2_2") (pintype "passive"))
    )
    (net (code "105") (name "WR_NC") (class "Default")
      (node (ref "SV1") (pin "16") (pinfunction "16_16") (pintype "passive"))
    )
    (net (code "106") (name "X+") (class "Default")
      (node (ref "IC1") (pin "27") (pinfunction "PB1_27") (pintype "bidirectional"))
      (node (ref "J11") (pin "2") (pinfunction "2_2") (pintype "passive"))
      (node (ref "SV2") (pin "9") (pinfunction "9_9") (pintype "passive"))
    )
    (net (code "107") (name "X+_NC") (class "Default")
      (node (ref "SV1") (pin "12") (pinfunction "12_12") (pintype "passive"))
    )
    (net (code "108") (name "X-") (class "Default")
      (node (ref "IC1") (pin "24") (pinfunction "PC4_24") (pintype "bidirectional"))
      (node (ref "J11") (pin "4") (pinfunction "4_4") (pintype "passive"))
      (node (ref "SV2") (pin "7") (pinfunction "7_7") (pintype "passive"))
    )
    (net (code "109") (name "X-_NC") (class "Default")
      (node (ref "SV1") (pin "10") (pinfunction "10_10") (pintype "passive"))
    )
    (net (code "110") (name "Y+") (class "Default")
      (node (ref "IC1") (pin "26") (pinfunction "PB0_26") (pintype "bidirectional"))
      (node (ref "J11") (pin "1") (pinfunction "1_1") (pintype "passive"))
      (node (ref "SV2") (pin "10") (pinfunction "10_10") (pintype "passive"))
    )
    (net (code "111") (name "Y+_NC") (class "Default")
      (node (ref "SV1") (pin "11") (pinfunction "11_11") (pintype "passive"))
    )
    (net (code "112") (name "Y-") (class "Default")
      (node (ref "IC1") (pin "25") (pinfunction "PC5_25") (pintype "bidirectional"))
      (node (ref "J11") (pin "3") (pinfunction "3_3") (pintype "passive"))
      (node (ref "SV2") (pin "8") (pinfunction "8_8") (pintype "passive"))
    )
    (net (code "113") (name "Y-_NC") (class "Default")
      (node (ref "SV1") (pin "9") (pinfunction "9_9") (pintype "passive"))
    )
    (net (code "114") (name "unconnected-(IC1-PA0-Pad14)") (class "Default")
      (node (ref "IC1") (pin "14") (pinfunction "PA0_14") (pintype "bidirectional"))
    )
    (net (code "115") (name "unconnected-(IC1-PA1-Pad15)") (class "Default")
      (node (ref "IC1") (pin "15") (pinfunction "PA1_15") (pintype "bidirectional"))
    )
    (net (code "116") (name "unconnected-(IC1-PA2-Pad16)") (class "Default")
      (node (ref "IC1") (pin "16") (pinfunction "PA2_16") (pintype "bidirectional"))
    )
    (net (code "117") (name "unconnected-(IC1-PA3-Pad17)") (class "Default")
      (node (ref "IC1") (pin "17") (pinfunction "PA3_17") (pintype "bidirectional"))
    )
    (net (code "118") (name "unconnected-(IC1-PA15-Pad50)") (class "Default")
      (node (ref "IC1") (pin "50") (pinfunction "PA15_50") (pintype "bidirectional"))
    )
    (net (code "119") (name "unconnected-(IC1-PB2-Pad28)") (class "Default")
      (node (ref "IC1") (pin "28") (pinfunction "PB2_28") (pintype "bidirectional"))
    )
    (net (code "120") (name "unconnected-(IC1-PB10-Pad29)") (class "Default")
      (node (ref "IC1") (pin "29") (pinfunction "PB10_29") (pintype "bidirectional"))
    )
    (net (code "121") (name "unconnected-(IC1-PC13-Pad2)") (class "Default")
      (node (ref "IC1") (pin "2") (pinfunction "PC13_2") (pintype "bidirectional"))
    )
    (net (code "122") (name "unconnected-(IC1-PC14-_OSC32_IN-Pad3)") (class "Default")
      (node (ref "IC1") (pin "3") (pinfunction "PC14-_OSC32_IN_3") (pintype "bidirectional"))
    )
    (net (code "123") (name "unconnected-(IC1-PC15-OSC32_OUT-Pad4)") (class "Default")
      (node (ref "IC1") (pin "4") (pinfunction "PC15-OSC32_OUT_4") (pintype "bidirectional"))
    )
    (net (code "124") (name "unconnected-(IC1-PD2-Pad54)") (class "Default")
      (node (ref "IC1") (pin "54") (pinfunction "PD2_54") (pintype "bidirectional"))
    )
    (net (code "125") (name "unconnected-(IC4-XO-Pad13)") (class "Default")
      (node (ref "IC4") (pin "13") (pinfunction "XO_13") (pintype "bidirectional"))
    )
  )
)
